# kinks_v41.net
KiCad netlist of a schematic drawn in EAGLE
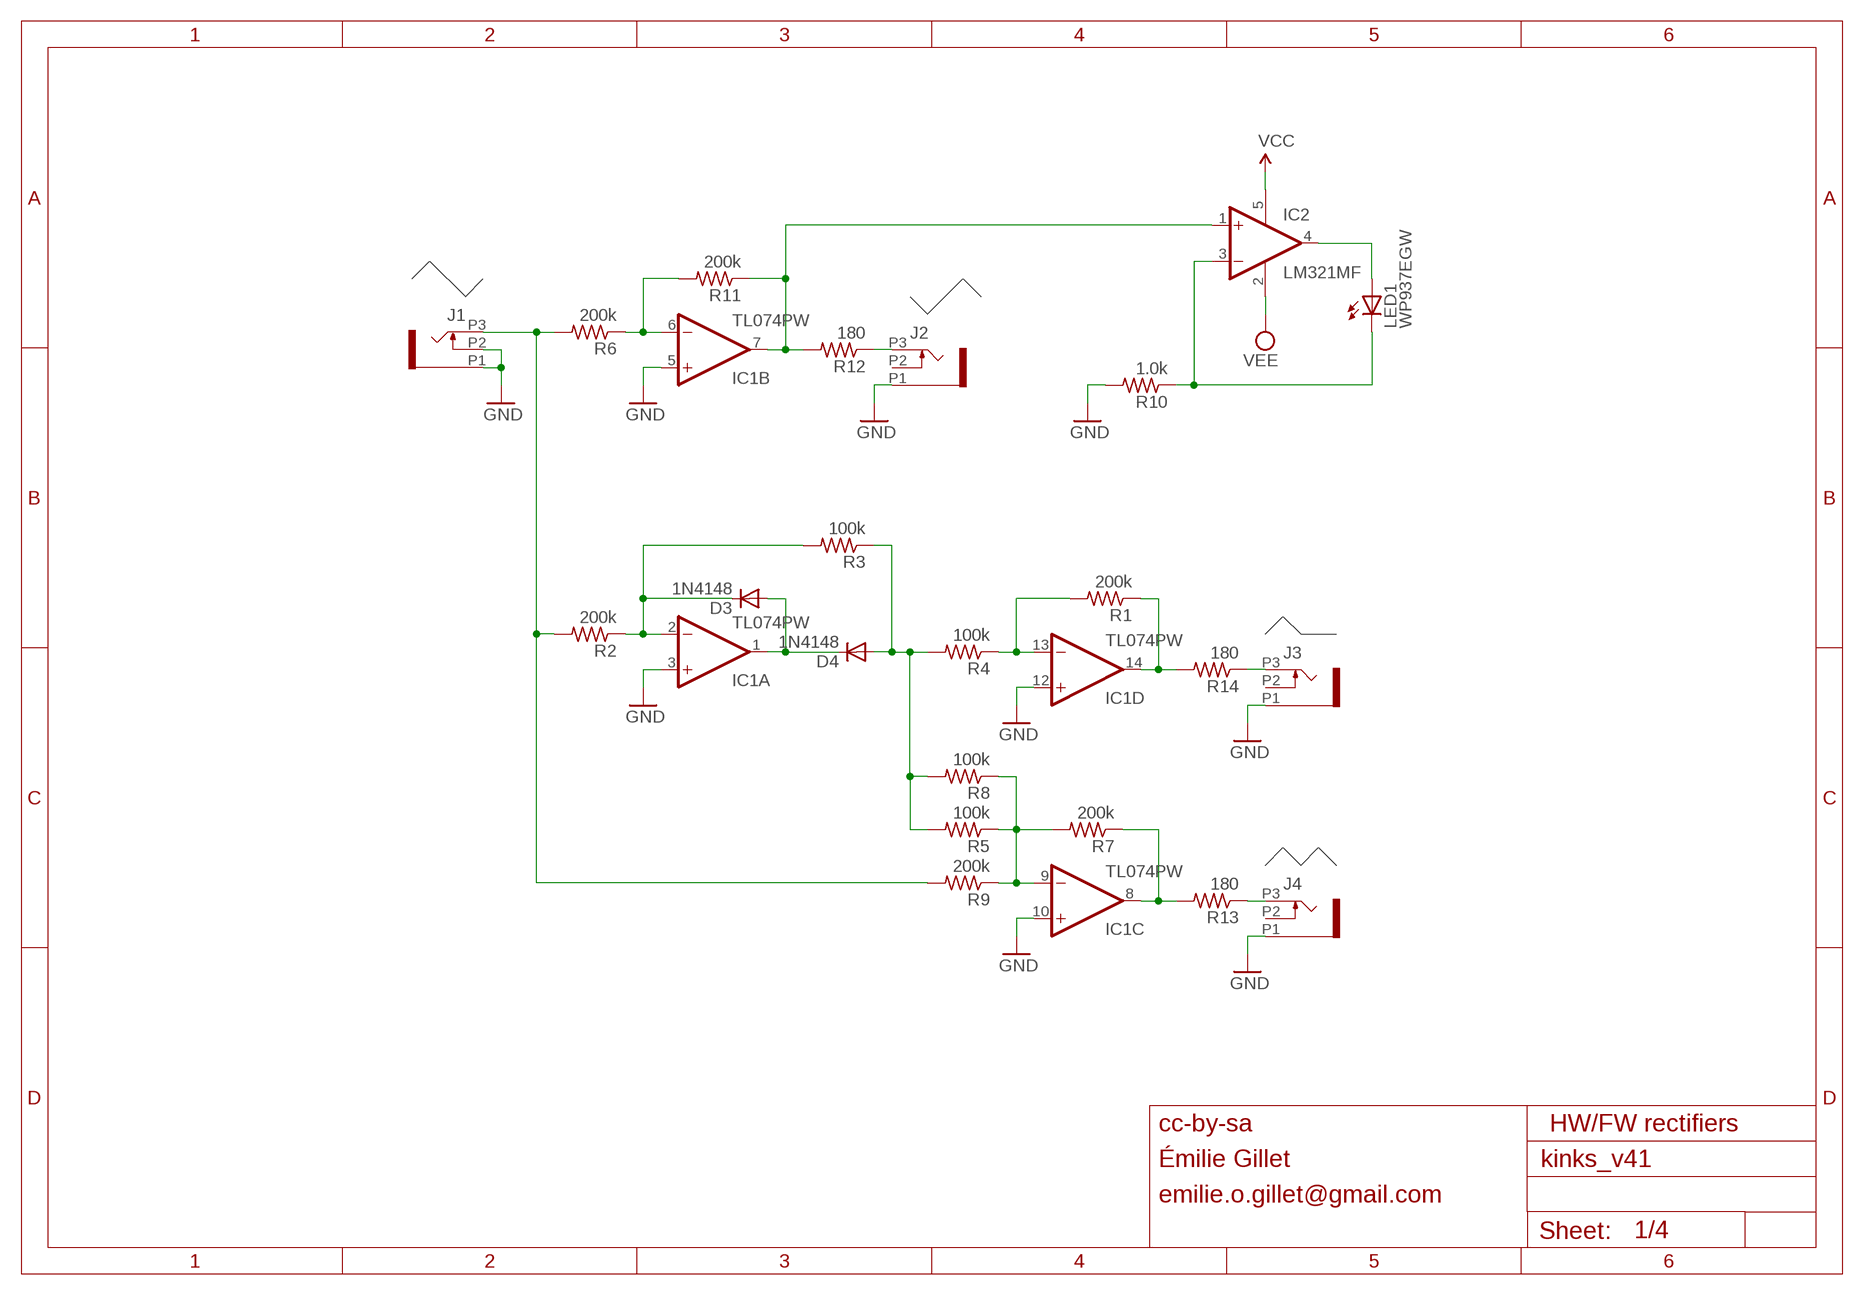
[diagram p0: schematic, sheet 1]
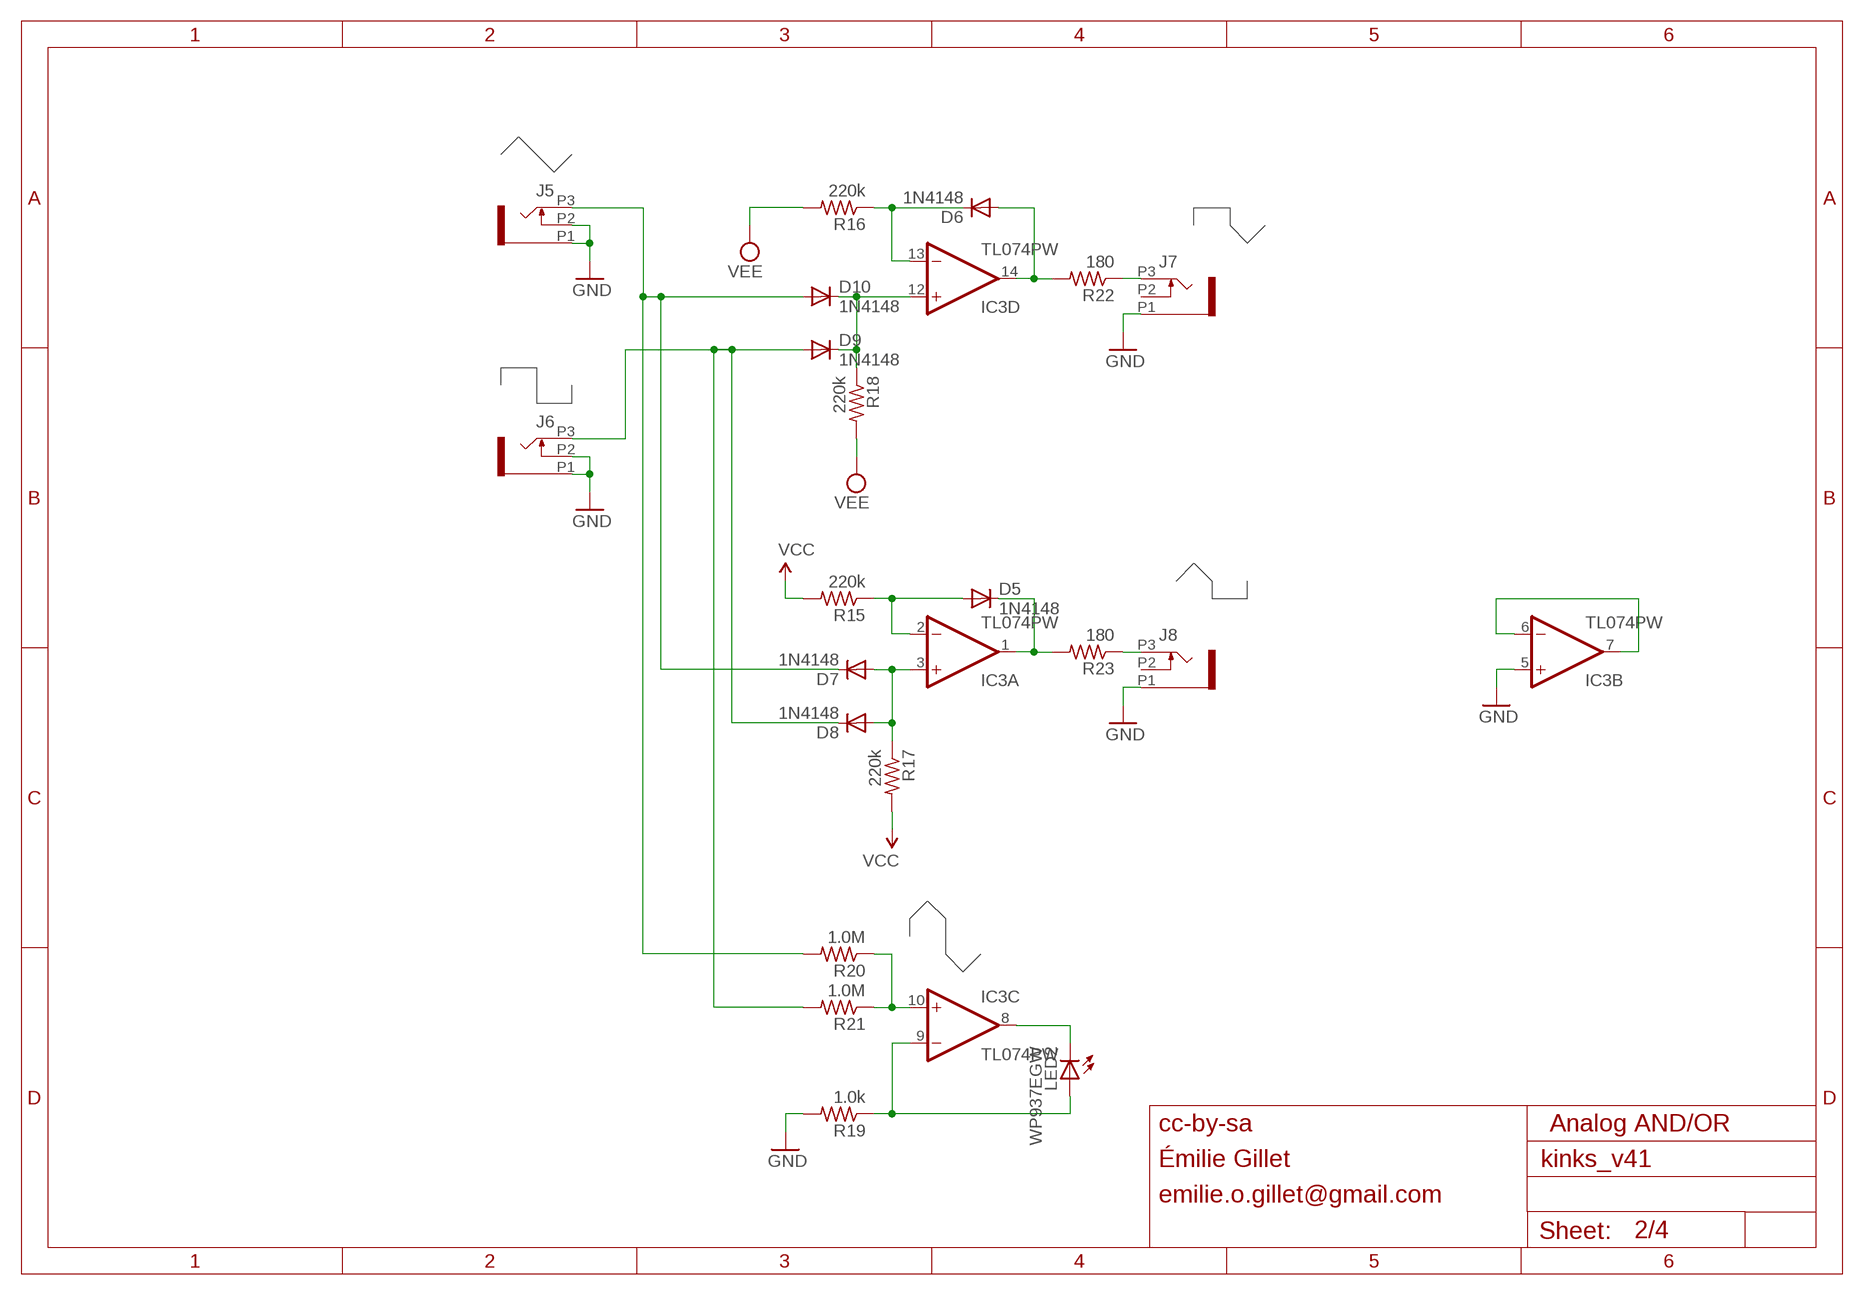
[diagram p1: schematic, sheet 2]
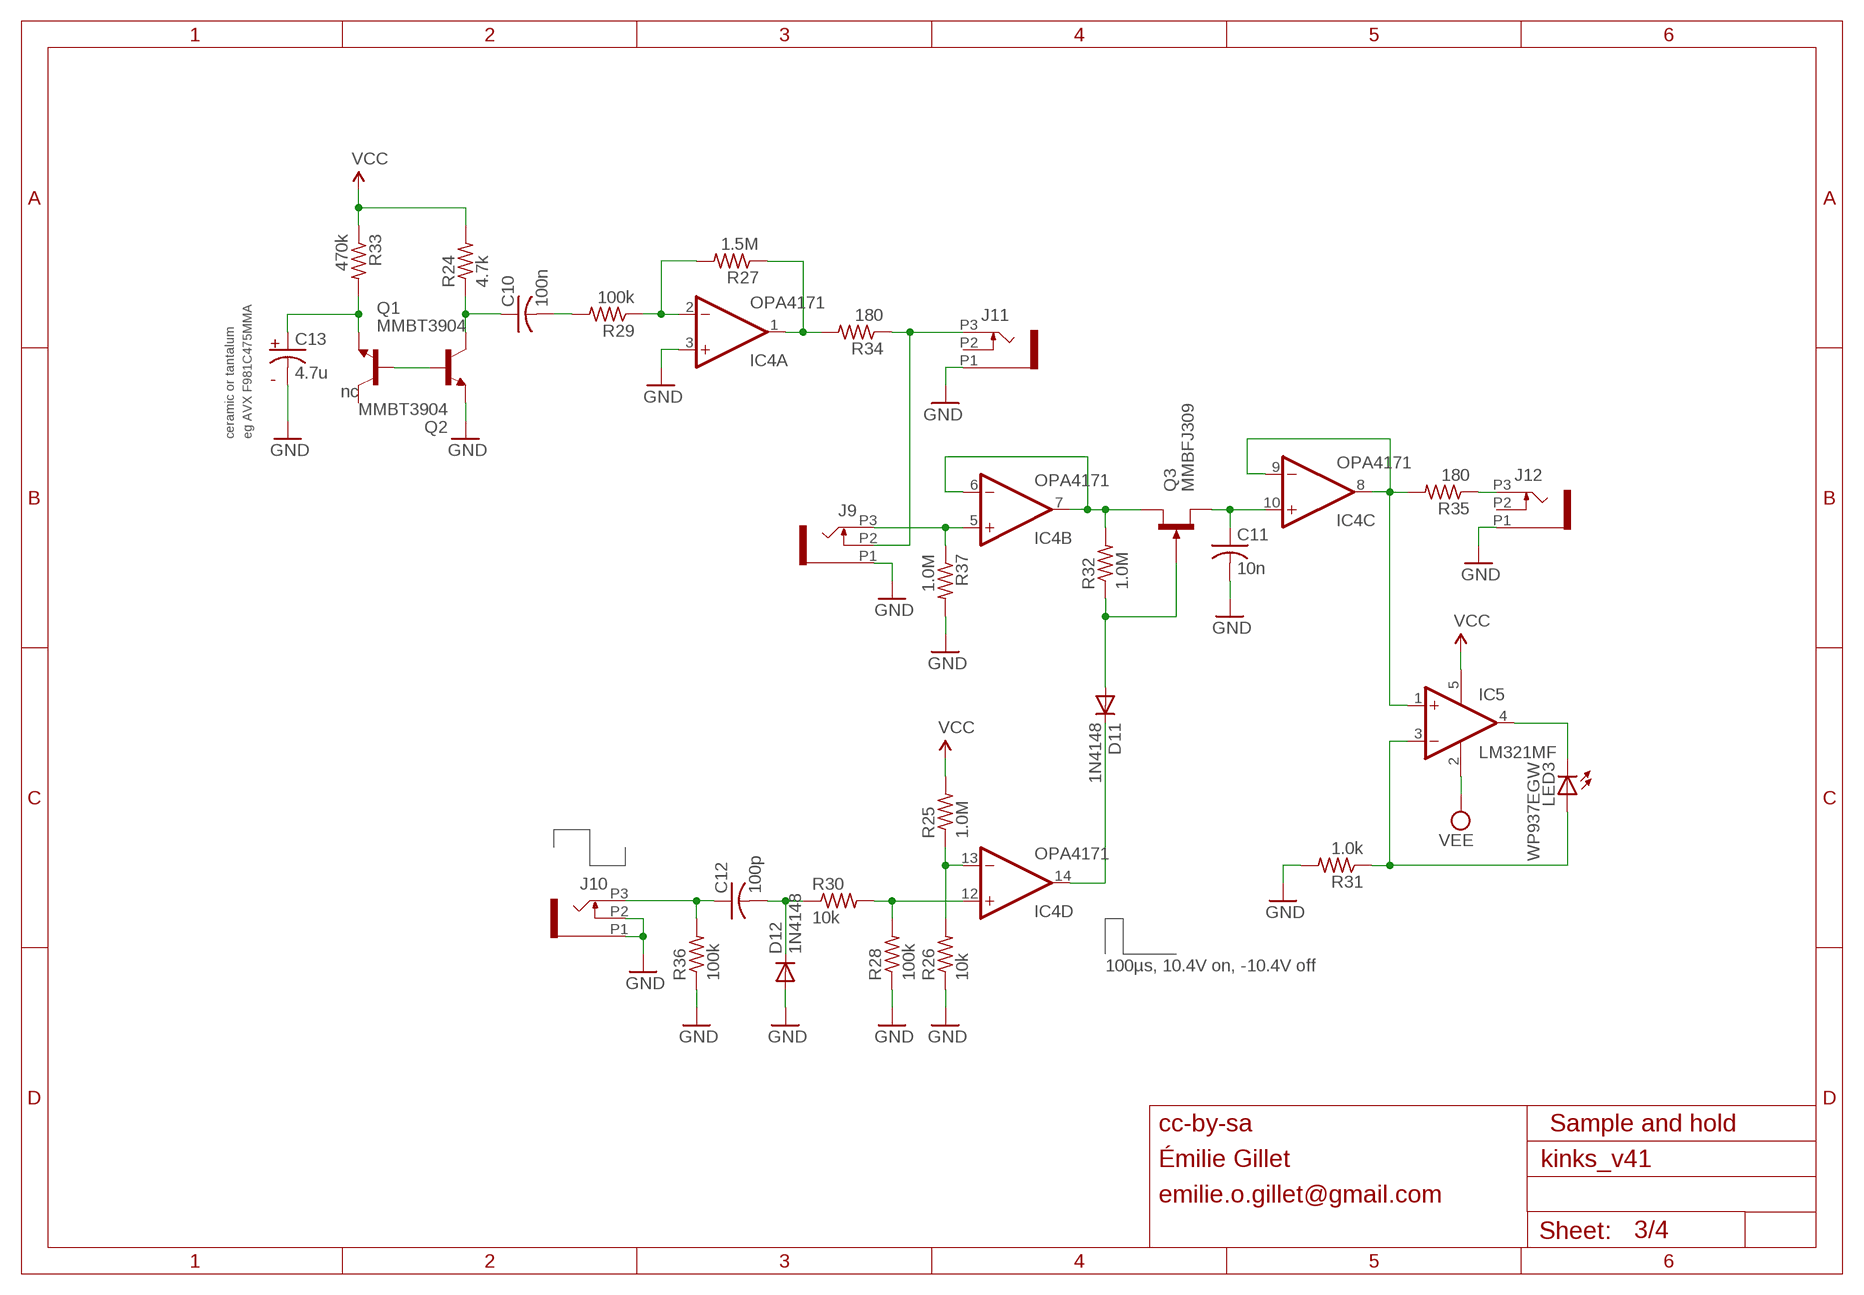
[diagram p2: schematic, sheet 3]
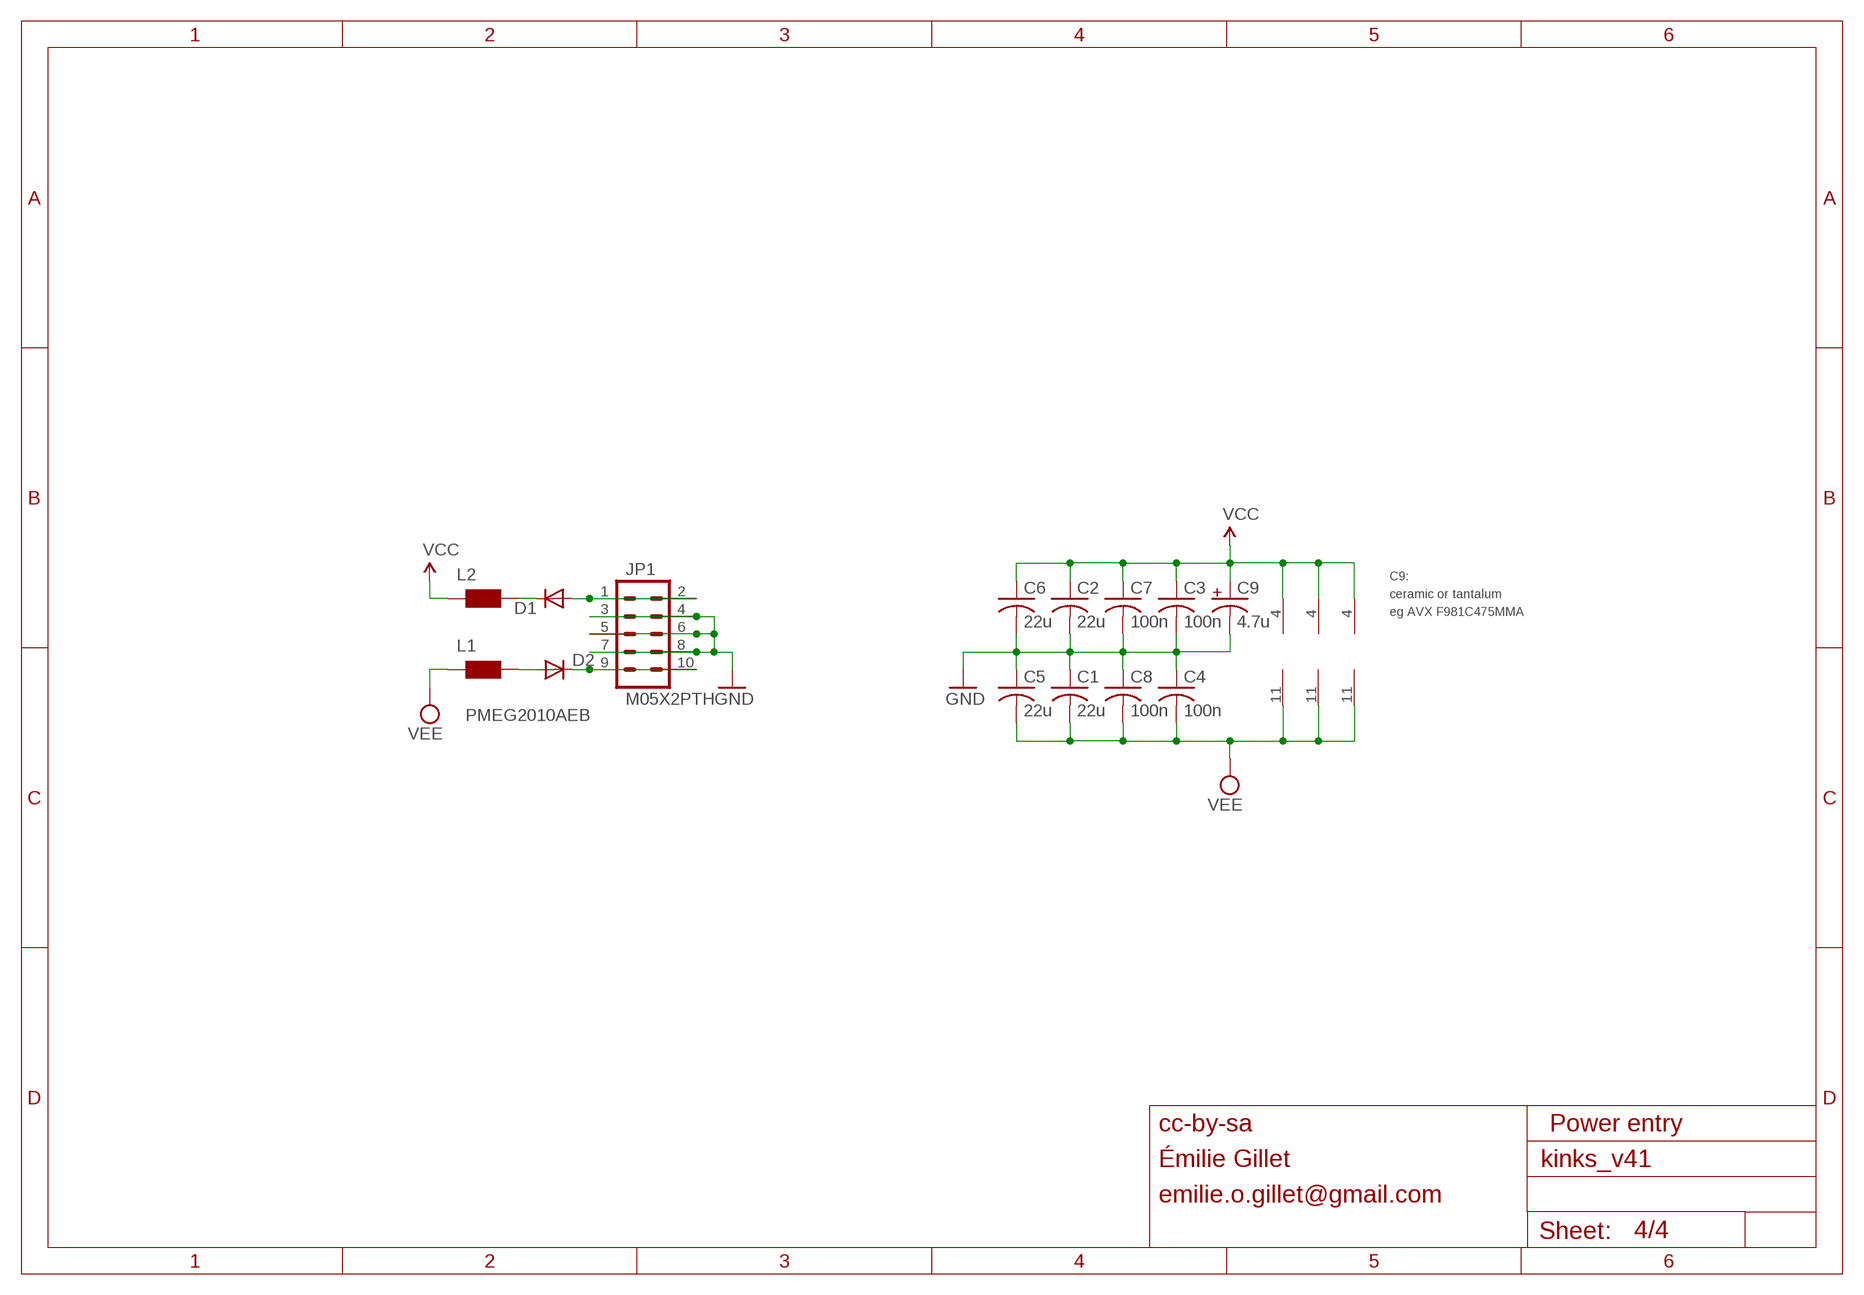
[diagram p3: schematic, sheet 4]

(export (version "E")
  (design (tool "Eeschema 10.0.6"))
  (components
    (comp (ref "C1")
      (value "22u")
      (footprint "eagle-import:C0805")
      (libsource (lib "eagle-import") (part "C-USC0805"))
    )
    (comp (ref "C2")
      (value "22u")
      (footprint "eagle-import:C0805")
      (libsource (lib "eagle-import") (part "C-USC0805"))
    )
    (comp (ref "C3")
      (value "100n")
      (footprint "eagle-import:C0402")
      (libsource (lib "eagle-import") (part "C-USC0402"))
    )
    (comp (ref "C4")
      (value "100n")
      (footprint "eagle-import:C0402")
      (libsource (lib "eagle-import") (part "C-USC0402"))
    )
    (comp (ref "C5")
      (value "22u")
      (footprint "eagle-import:C0805")
      (libsource (lib "eagle-import") (part "C-USC0805"))
    )
    (comp (ref "C6")
      (value "22u")
      (footprint "eagle-import:C0805")
      (libsource (lib "eagle-import") (part "C-USC0805"))
    )
    (comp (ref "C7")
      (value "100n")
      (footprint "eagle-import:C0402")
      (libsource (lib "eagle-import") (part "C-USC0402"))
    )
    (comp (ref "C8")
      (value "100n")
      (footprint "eagle-import:C0402")
      (libsource (lib "eagle-import") (part "C-USC0402"))
    )
    (comp (ref "C9")
      (value "4.7u")
      (footprint "eagle-import:C0603")
      (libsource (lib "eagle-import") (part "C-USC0603"))
    )
    (comp (ref "D1")
      (value "PMEG2010AEB")
      (footprint "eagle-import:SOD523")
      (libsource (lib "eagle-import") (part "DIODE-SOD523"))
    )
    (comp (ref "D2")
      (value "PMEG2010AEB")
      (footprint "eagle-import:SOD523")
      (libsource (lib "eagle-import") (part "DIODE-SOD523"))
    )
    (comp (ref "IC1")
      (value "TL074PW")
      (footprint "eagle-import:TSSOP14")
      (libsource (lib "eagle-import") (part "TL074PW"))
    )
    (comp (ref "IC3")
      (value "TL074PW")
      (footprint "eagle-import:TSSOP14")
      (libsource (lib "eagle-import") (part "TL074PW"))
    )
    (comp (ref "IC4")
      (value "OPA4171")
      (footprint "eagle-import:TSSOP14")
      (libsource (lib "eagle-import") (part "TL074PW"))
    )
    (comp (ref "JP1")
      (value "M05X2PTH")
      (footprint "eagle-import:AVR_ICSP")
      (libsource (lib "eagle-import") (part "M05X2PTH"))
    )
    (comp (ref "L1")
      (value "WE-CBF_0603")
      (footprint "eagle-import:0603")
      (libsource (lib "eagle-import") (part "WE-CBF_0603"))
    )
    (comp (ref "L2")
      (value "WE-CBF_0603")
      (footprint "eagle-import:0603")
      (libsource (lib "eagle-import") (part "WE-CBF_0603"))
    )
    (comp (ref "C10")
      (value "100n")
      (footprint "eagle-import:C0402")
      (libsource (lib "eagle-import") (part "C-USC0402"))
    )
    (comp (ref "C11")
      (value "10n")
      (footprint "eagle-import:C0603")
      (libsource (lib "eagle-import") (part "C-USC0603"))
    )
    (comp (ref "C12")
      (value "100p")
      (footprint "eagle-import:C0402")
      (libsource (lib "eagle-import") (part "C-USC0402"))
    )
    (comp (ref "C13")
      (value "4.7u")
      (footprint "eagle-import:C0603")
      (libsource (lib "eagle-import") (part "C-USC0603"))
    )
    (comp (ref "D11")
      (value "1N4148")
      (footprint "eagle-import:SOD523")
      (libsource (lib "eagle-import") (part "DIODE-SOD523"))
    )
    (comp (ref "D12")
      (value "1N4148")
      (footprint "eagle-import:SOD523")
      (libsource (lib "eagle-import") (part "DIODE-SOD523"))
    )
    (comp (ref "IC5")
      (value "LM321MF")
      (footprint "eagle-import:SOT23-5")
      (libsource (lib "eagle-import") (part "LM321?MF"))
    )
    (comp (ref "J9")
      (value "PJ301_THONKICONN6")
      (footprint "eagle-import:WQP_PJ_301M6")
      (libsource (lib "eagle-import") (part "PJ301_THONKICONN6"))
    )
    (comp (ref "J10")
      (value "PJ301_THONKICONN6")
      (footprint "eagle-import:WQP_PJ_301M6")
      (libsource (lib "eagle-import") (part "PJ301_THONKICONN6"))
    )
    (comp (ref "J11")
      (value "PJ301_THONKICONN6")
      (footprint "eagle-import:WQP_PJ_301M6")
      (libsource (lib "eagle-import") (part "PJ301_THONKICONN6"))
    )
    (comp (ref "J12")
      (value "PJ301_THONKICONN6")
      (footprint "eagle-import:WQP_PJ_301M6")
      (libsource (lib "eagle-import") (part "PJ301_THONKICONN6"))
    )
    (comp (ref "LED3")
      (value "WP937EGW")
      (footprint "eagle-import:LED3MM")
      (libsource (lib "eagle-import") (part "LED3MM"))
    )
    (comp (ref "Q1")
      (value "MMBT3904")
      (footprint "eagle-import:SOT23-BEC")
      (libsource (lib "eagle-import") (part "-NPN-SOT23-BECMMBT3904LT1"))
    )
    (comp (ref "Q2")
      (value "MMBT3904")
      (footprint "eagle-import:SOT23-BEC")
      (libsource (lib "eagle-import") (part "-NPN-SOT23-BECMMBT3904LT1"))
    )
    (comp (ref "Q3")
      (value "MMBFJ309")
      (footprint "eagle-import:SOT23")
      (libsource (lib "eagle-import") (part "MMBFJ3"))
    )
    (comp (ref "R24")
      (value "4.7k")
      (footprint "eagle-import:R0402")
      (libsource (lib "eagle-import") (part "R-US_R0402"))
    )
    (comp (ref "R25")
      (value "1.0M")
      (footprint "eagle-import:R0402")
      (libsource (lib "eagle-import") (part "R-US_R0402"))
    )
    (comp (ref "R26")
      (value "10k")
      (footprint "eagle-import:R0402")
      (libsource (lib "eagle-import") (part "R-US_R0402"))
    )
    (comp (ref "R27")
      (value "1.5M")
      (footprint "eagle-import:R0402")
      (libsource (lib "eagle-import") (part "R-US_R0402"))
    )
    (comp (ref "R28")
      (value "100k")
      (footprint "eagle-import:R0402")
      (libsource (lib "eagle-import") (part "R-US_R0402"))
    )
    (comp (ref "R29")
      (value "100k")
      (footprint "eagle-import:R0402")
      (libsource (lib "eagle-import") (part "R-US_R0402"))
    )
    (comp (ref "R30")
      (value "10k")
      (footprint "eagle-import:R0402")
      (libsource (lib "eagle-import") (part "R-US_R0402"))
    )
    (comp (ref "R31")
      (value "1.0k")
      (footprint "eagle-import:R0402")
      (libsource (lib "eagle-import") (part "R-US_R0402"))
    )
    (comp (ref "R32")
      (value "1.0M")
      (footprint "eagle-import:R0402")
      (libsource (lib "eagle-import") (part "R-US_R0402"))
    )
    (comp (ref "R33")
      (value "470k")
      (footprint "eagle-import:R0402")
      (libsource (lib "eagle-import") (part "R-US_R0402"))
    )
    (comp (ref "R34")
      (value "180")
      (footprint "eagle-import:R0402")
      (libsource (lib "eagle-import") (part "R-US_R0402"))
    )
    (comp (ref "R35")
      (value "180")
      (footprint "eagle-import:R0402")
      (libsource (lib "eagle-import") (part "R-US_R0402"))
    )
    (comp (ref "R36")
      (value "100k")
      (footprint "eagle-import:R0402")
      (libsource (lib "eagle-import") (part "R-US_R0402"))
    )
    (comp (ref "R37")
      (value "1.0M")
      (footprint "eagle-import:R0402")
      (libsource (lib "eagle-import") (part "R-US_R0402"))
    )
    (comp (ref "D5")
      (value "1N4148")
      (footprint "eagle-import:SOD523")
      (libsource (lib "eagle-import") (part "DIODE-SOD523"))
    )
    (comp (ref "D6")
      (value "1N4148")
      (footprint "eagle-import:SOD523")
      (libsource (lib "eagle-import") (part "DIODE-SOD523"))
    )
    (comp (ref "D7")
      (value "1N4148")
      (footprint "eagle-import:SOD523")
      (libsource (lib "eagle-import") (part "DIODE-SOD523"))
    )
    (comp (ref "D8")
      (value "1N4148")
      (footprint "eagle-import:SOD523")
      (libsource (lib "eagle-import") (part "DIODE-SOD523"))
    )
    (comp (ref "D9")
      (value "1N4148")
      (footprint "eagle-import:SOD523")
      (libsource (lib "eagle-import") (part "DIODE-SOD523"))
    )
    (comp (ref "D10")
      (value "1N4148")
      (footprint "eagle-import:SOD523")
      (libsource (lib "eagle-import") (part "DIODE-SOD523"))
    )
    (comp (ref "J5")
      (value "PJ301_THONKICONN6")
      (footprint "eagle-import:WQP_PJ_301M6")
      (libsource (lib "eagle-import") (part "PJ301_THONKICONN6"))
    )
    (comp (ref "J6")
      (value "PJ301_THONKICONN6")
      (footprint "eagle-import:WQP_PJ_301M6")
      (libsource (lib "eagle-import") (part "PJ301_THONKICONN6"))
    )
    (comp (ref "J7")
      (value "PJ301_THONKICONN6")
      (footprint "eagle-import:WQP_PJ_301M6")
      (libsource (lib "eagle-import") (part "PJ301_THONKICONN6"))
    )
    (comp (ref "J8")
      (value "PJ301_THONKICONN6")
      (footprint "eagle-import:WQP_PJ_301M6")
      (libsource (lib "eagle-import") (part "PJ301_THONKICONN6"))
    )
    (comp (ref "LED2")
      (value "WP937EGW")
      (footprint "eagle-import:LED3MM")
      (libsource (lib "eagle-import") (part "LED3MM"))
    )
    (comp (ref "R15")
      (value "220k")
      (footprint "eagle-import:R0402")
      (libsource (lib "eagle-import") (part "R-US_R0402"))
    )
    (comp (ref "R16")
      (value "220k")
      (footprint "eagle-import:R0402")
      (libsource (lib "eagle-import") (part "R-US_R0402"))
    )
    (comp (ref "R17")
      (value "220k")
      (footprint "eagle-import:R0402")
      (libsource (lib "eagle-import") (part "R-US_R0402"))
    )
    (comp (ref "R18")
      (value "220k")
      (footprint "eagle-import:R0402")
      (libsource (lib "eagle-import") (part "R-US_R0402"))
    )
    (comp (ref "R19")
      (value "1.0k")
      (footprint "eagle-import:R0402")
      (libsource (lib "eagle-import") (part "R-US_R0402"))
    )
    (comp (ref "R20")
      (value "1.0M")
      (footprint "eagle-import:R0402")
      (libsource (lib "eagle-import") (part "R-US_R0402"))
    )
    (comp (ref "R21")
      (value "1.0M")
      (footprint "eagle-import:R0402")
      (libsource (lib "eagle-import") (part "R-US_R0402"))
    )
    (comp (ref "R22")
      (value "180")
      (footprint "eagle-import:R0402")
      (libsource (lib "eagle-import") (part "R-US_R0402"))
    )
    (comp (ref "R23")
      (value "180")
      (footprint "eagle-import:R0402")
      (libsource (lib "eagle-import") (part "R-US_R0402"))
    )
    (comp (ref "D3")
      (value "1N4148")
      (footprint "eagle-import:SOD523")
      (libsource (lib "eagle-import") (part "DIODE-SOD523"))
    )
    (comp (ref "D4")
      (value "1N4148")
      (footprint "eagle-import:SOD523")
      (libsource (lib "eagle-import") (part "DIODE-SOD523"))
    )
    (comp (ref "IC2")
      (value "LM321MF")
      (footprint "eagle-import:SOT23-5")
      (libsource (lib "eagle-import") (part "LM321?MF"))
    )
    (comp (ref "J1")
      (value "PJ301_THONKICONN6")
      (footprint "eagle-import:WQP_PJ_301M6")
      (libsource (lib "eagle-import") (part "PJ301_THONKICONN6"))
    )
    (comp (ref "J2")
      (value "PJ301_THONKICONN6")
      (footprint "eagle-import:WQP_PJ_301M6")
      (libsource (lib "eagle-import") (part "PJ301_THONKICONN6"))
    )
    (comp (ref "J3")
      (value "PJ301_THONKICONN6")
      (footprint "eagle-import:WQP_PJ_301M6")
      (libsource (lib "eagle-import") (part "PJ301_THONKICONN6"))
    )
    (comp (ref "J4")
      (value "PJ301_THONKICONN6")
      (footprint "eagle-import:WQP_PJ_301M6")
      (libsource (lib "eagle-import") (part "PJ301_THONKICONN6"))
    )
    (comp (ref "LED1")
      (value "WP937EGW")
      (footprint "eagle-import:LED3MM")
      (libsource (lib "eagle-import") (part "LED3MM"))
    )
    (comp (ref "R1")
      (value "200k")
      (footprint "eagle-import:R0402")
      (libsource (lib "eagle-import") (part "R-US_R0402"))
    )
    (comp (ref "R2")
      (value "200k")
      (footprint "eagle-import:R0402")
      (libsource (lib "eagle-import") (part "R-US_R0402"))
    )
    (comp (ref "R3")
      (value "100k")
      (footprint "eagle-import:R0402")
      (libsource (lib "eagle-import") (part "R-US_R0402"))
    )
    (comp (ref "R4")
      (value "100k")
      (footprint "eagle-import:R0402")
      (libsource (lib "eagle-import") (part "R-US_R0402"))
    )
    (comp (ref "R5")
      (value "100k")
      (footprint "eagle-import:R0402")
      (libsource (lib "eagle-import") (part "R-US_R0402"))
    )
    (comp (ref "R6")
      (value "200k")
      (footprint "eagle-import:R0402")
      (libsource (lib "eagle-import") (part "R-US_R0402"))
    )
    (comp (ref "R7")
      (value "200k")
      (footprint "eagle-import:R0402")
      (libsource (lib "eagle-import") (part "R-US_R0402"))
    )
    (comp (ref "R8")
      (value "100k")
      (footprint "eagle-import:R0402")
      (libsource (lib "eagle-import") (part "R-US_R0402"))
    )
    (comp (ref "R9")
      (value "200k")
      (footprint "eagle-import:R0402")
      (libsource (lib "eagle-import") (part "R-US_R0402"))
    )
    (comp (ref "R10")
      (value "1.0k")
      (footprint "eagle-import:R0402")
      (libsource (lib "eagle-import") (part "R-US_R0402"))
    )
    (comp (ref "R11")
      (value "200k")
      (footprint "eagle-import:R0402")
      (libsource (lib "eagle-import") (part "R-US_R0402"))
    )
    (comp (ref "R12")
      (value "180")
      (footprint "eagle-import:R0402")
      (libsource (lib "eagle-import") (part "R-US_R0402"))
    )
    (comp (ref "R13")
      (value "180")
      (footprint "eagle-import:R0402")
      (libsource (lib "eagle-import") (part "R-US_R0402"))
    )
    (comp (ref "R14")
      (value "180")
      (footprint "eagle-import:R0402")
      (libsource (lib "eagle-import") (part "R-US_R0402"))
    )
  )
  (nets
    (net (code "1") (name "GND") (class "Default")
      (node (ref "C1") (pin "1") (pinfunction "1_1") (pintype "passive"))
      (node (ref "C11") (pin "2") (pinfunction "2_2") (pintype "passive"))
      (node (ref "C13") (pin "2") (pinfunction "2_2") (pintype "passive"))
      (node (ref "C2") (pin "2") (pinfunction "2_2") (pintype "passive"))
      (node (ref "C3") (pin "2") (pinfunction "2_2") (pintype "passive"))
      (node (ref "C4") (pin "1") (pinfunction "1_1") (pintype "passive"))
      (node (ref "C5") (pin "1") (pinfunction "1_1") (pintype "passive"))
      (node (ref "C6") (pin "2") (pinfunction "2_2") (pintype "passive"))
      (node (ref "C7") (pin "2") (pinfunction "2_2") (pintype "passive"))
      (node (ref "C8") (pin "1") (pinfunction "1_1") (pintype "passive"))
      (node (ref "C9") (pin "2") (pinfunction "2_2") (pintype "passive"))
      (node (ref "D12") (pin "A") (pinfunction "A_A") (pintype "passive"))
      (node (ref "IC1") (pin "10") (pinfunction "+IN_10") (pintype "input"))
      (node (ref "IC1") (pin "12") (pinfunction "+IN_12") (pintype "input"))
      (node (ref "IC1") (pin "3") (pinfunction "+IN_3") (pintype "input"))
      (node (ref "IC1") (pin "5") (pinfunction "+IN_5") (pintype "input"))
      (node (ref "IC3") (pin "5") (pinfunction "+IN_5") (pintype "input"))
      (node (ref "IC4") (pin "3") (pinfunction "+IN_3") (pintype "input"))
      (node (ref "J1") (pin "P1") (pinfunction "1_P1") (pintype "passive"))
      (node (ref "J1") (pin "P2") (pinfunction "2_P2") (pintype "passive"))
      (node (ref "J10") (pin "P1") (pinfunction "1_P1") (pintype "passive"))
      (node (ref "J10") (pin "P2") (pinfunction "2_P2") (pintype "passive"))
      (node (ref "J11") (pin "P1") (pinfunction "1_P1") (pintype "passive"))
      (node (ref "J12") (pin "P1") (pinfunction "1_P1") (pintype "passive"))
      (node (ref "J2") (pin "P1") (pinfunction "1_P1") (pintype "passive"))
      (node (ref "J3") (pin "P1") (pinfunction "1_P1") (pintype "passive"))
      (node (ref "J4") (pin "P1") (pinfunction "1_P1") (pintype "passive"))
      (node (ref "J5") (pin "P1") (pinfunction "1_P1") (pintype "passive"))
      (node (ref "J5") (pin "P2") (pinfunction "2_P2") (pintype "passive"))
      (node (ref "J6") (pin "P1") (pinfunction "1_P1") (pintype "passive"))
      (node (ref "J6") (pin "P2") (pinfunction "2_P2") (pintype "passive"))
      (node (ref "J7") (pin "P1") (pinfunction "1_P1") (pintype "passive"))
      (node (ref "J8") (pin "P1") (pinfunction "1_P1") (pintype "passive"))
      (node (ref "J9") (pin "P1") (pinfunction "1_P1") (pintype "passive"))
      (node (ref "JP1") (pin "3") (pinfunction "3_3") (pintype "passive"))
      (node (ref "JP1") (pin "4") (pinfunction "4_4") (pintype "passive"))
      (node (ref "JP1") (pin "5") (pinfunction "5_5") (pintype "passive"))
      (node (ref "JP1") (pin "6") (pinfunction "6_6") (pintype "passive"))
      (node (ref "JP1") (pin "7") (pinfunction "7_7") (pintype "passive"))
      (node (ref "JP1") (pin "8") (pinfunction "8_8") (pintype "passive"))
      (node (ref "Q1") (pin "E") (pinfunction "E_E") (pintype "passive"))
      (node (ref "R10") (pin "2") (pinfunction "2_2") (pintype "passive"))
      (node (ref "R19") (pin "2") (pinfunction "2_2") (pintype "passive"))
      (node (ref "R26") (pin "1") (pinfunction "1_1") (pintype "passive"))
      (node (ref "R28") (pin "1") (pinfunction "1_1") (pintype "passive"))
      (node (ref "R31") (pin "2") (pinfunction "2_2") (pintype "passive"))
      (node (ref "R36") (pin "1") (pinfunction "1_1") (pintype "passive"))
      (node (ref "R37") (pin "2") (pinfunction "2_2") (pintype "passive"))
    )
    (net (code "2") (name "Net-(C10-Pad1)") (class "Default")
      (node (ref "C10") (pin "1") (pinfunction "1_1") (pintype "passive"))
      (node (ref "Q1") (pin "C") (pinfunction "C_C") (pintype "passive"))
      (node (ref "R24") (pin "1") (pinfunction "1_1") (pintype "passive"))
    )
    (net (code "3") (name "Net-(C10-Pad2)") (class "Default")
      (node (ref "C10") (pin "2") (pinfunction "2_2") (pintype "passive"))
      (node (ref "R29") (pin "2") (pinfunction "2_2") (pintype "passive"))
    )
    (net (code "4") (name "Net-(C12-Pad2)") (class "Default")
      (node (ref "C12") (pin "2") (pinfunction "2_2") (pintype "passive"))
      (node (ref "D12") (pin "C") (pinfunction "C_C") (pintype "passive"))
      (node (ref "R30") (pin "1") (pinfunction "1_1") (pintype "passive"))
    )
    (net (code "5") (name "Net-(C13-Pad1)") (class "Default")
      (node (ref "C13") (pin "1") (pinfunction "1_1") (pintype "passive"))
      (node (ref "Q2") (pin "E") (pinfunction "E_E") (pintype "passive"))
      (node (ref "R33") (pin "2") (pinfunction "2_2") (pintype "passive"))
    )
    (net (code "6") (name "Net-(D1-PadA)") (class "Default")
      (node (ref "D1") (pin "A") (pinfunction "A_A") (pintype "passive"))
      (node (ref "JP1") (pin "1") (pinfunction "1_1") (pintype "passive"))
      (node (ref "JP1") (pin "2") (pinfunction "2_2") (pintype "passive"))
    )
    (net (code "7") (name "Net-(D1-PadC)") (class "Default")
      (node (ref "D1") (pin "C") (pinfunction "C_C") (pintype "passive"))
      (node (ref "L2") (pin "2") (pinfunction "2_2") (pintype "passive"))
    )
    (net (code "8") (name "Net-(D2-PadA)") (class "Default")
      (node (ref "D2") (pin "A") (pinfunction "A_A") (pintype "passive"))
      (node (ref "L1") (pin "2") (pinfunction "2_2") (pintype "passive"))
    )
    (net (code "9") (name "Net-(D2-PadC)") (class "Default")
      (node (ref "D2") (pin "C") (pinfunction "C_C") (pintype "passive"))
      (node (ref "JP1") (pin "10") (pinfunction "10_10") (pintype "passive"))
      (node (ref "JP1") (pin "9") (pinfunction "9_9") (pintype "passive"))
    )
    (net (code "10") (name "Net-(D4-PadA)") (class "Default")
      (node (ref "D4") (pin "A") (pinfunction "A_A") (pintype "passive"))
      (node (ref "R3") (pin "1") (pinfunction "1_1") (pintype "passive"))
      (node (ref "R4") (pin "2") (pinfunction "2_2") (pintype "passive"))
      (node (ref "R5") (pin "2") (pinfunction "2_2") (pintype "passive"))
      (node (ref "R8") (pin "2") (pinfunction "2_2") (pintype "passive"))
    )
    (net (code "11") (name "Net-(IC1A--IN)") (class "Default")
      (node (ref "D3") (pin "C") (pinfunction "C_C") (pintype "passive"))
      (node (ref "IC1") (pin "2") (pinfunction "-IN_2") (pintype "input"))
      (node (ref "R2") (pin "1") (pinfunction "1_1") (pintype "passive"))
      (node (ref "R3") (pin "2") (pinfunction "2_2") (pintype "passive"))
    )
    (net (code "12") (name "Net-(IC1A-OUT)") (class "Default")
      (node (ref "D3") (pin "A") (pinfunction "A_A") (pintype "passive"))
      (node (ref "D4") (pin "C") (pinfunction "C_C") (pintype "passive"))
      (node (ref "IC1") (pin "1") (pinfunction "OUT_1") (pintype "output"))
    )
    (net (code "13") (name "Net-(IC1B--IN)") (class "Default")
      (node (ref "IC1") (pin "6") (pinfunction "-IN_6") (pintype "input"))
      (node (ref "R11") (pin "2") (pinfunction "2_2") (pintype "passive"))
      (node (ref "R6") (pin "1") (pinfunction "1_1") (pintype "passive"))
    )
    (net (code "14") (name "Net-(IC1B-OUT)") (class "Default")
      (node (ref "IC1") (pin "7") (pinfunction "OUT_7") (pintype "output"))
      (node (ref "IC2") (pin "1") (pinfunction "+IN_1") (pintype "input"))
      (node (ref "R11") (pin "1") (pinfunction "1_1") (pintype "passive"))
      (node (ref "R12") (pin "2") (pinfunction "2_2") (pintype "passive"))
    )
    (net (code "15") (name "Net-(IC1C--IN)") (class "Default")
      (node (ref "IC1") (pin "9") (pinfunction "-IN_9") (pintype "input"))
      (node (ref "R5") (pin "1") (pinfunction "1_1") (pintype "passive"))
      (node (ref "R7") (pin "2") (pinfunction "2_2") (pintype "passive"))
      (node (ref "R8") (pin "1") (pinfunction "1_1") (pintype "passive"))
      (node (ref "R9") (pin "1") (pinfunction "1_1") (pintype "passive"))
    )
    (net (code "16") (name "Net-(IC1C-OUT)") (class "Default")
      (node (ref "IC1") (pin "8") (pinfunction "OUT_8") (pintype "output"))
      (node (ref "R13") (pin "2") (pinfunction "2_2") (pintype "passive"))
      (node (ref "R7") (pin "1") (pinfunction "1_1") (pintype "passive"))
    )
    (net (code "17") (name "Net-(IC1D--IN)") (class "Default")
      (node (ref "IC1") (pin "13") (pinfunction "-IN_13") (pintype "input"))
      (node (ref "R1") (pin "2") (pinfunction "2_2") (pintype "passive"))
      (node (ref "R4") (pin "1") (pinfunction "1_1") (pintype "passive"))
    )
    (net (code "18") (name "Net-(IC1D-OUT)") (class "Default")
      (node (ref "IC1") (pin "14") (pinfunction "OUT_14") (pintype "output"))
      (node (ref "R1") (pin "1") (pinfunction "1_1") (pintype "passive"))
      (node (ref "R14") (pin "2") (pinfunction "2_2") (pintype "passive"))
    )
    (net (code "19") (name "Net-(IC2--IN)") (class "Default")
      (node (ref "IC2") (pin "3") (pinfunction "-IN_3") (pintype "input"))
      (node (ref "LED1") (pin "K") (pinfunction "C_K") (pintype "passive"))
      (node (ref "R10") (pin "1") (pinfunction "1_1") (pintype "passive"))
    )
    (net (code "20") (name "Net-(IC2-OUT)") (class "Default")
      (node (ref "IC2") (pin "4") (pinfunction "OUT_4") (pintype "output"))
      (node (ref "LED1") (pin "A") (pinfunction "A_A") (pintype "passive"))
    )
    (net (code "21") (name "Net-(IC3A-+IN)") (class "Default")
      (node (ref "D7") (pin "A") (pinfunction "A_A") (pintype "passive"))
      (node (ref "D8") (pin "A") (pinfunction "A_A") (pintype "passive"))
      (node (ref "IC3") (pin "3") (pinfunction "+IN_3") (pintype "input"))
      (node (ref "R17") (pin "1") (pinfunction "1_1") (pintype "passive"))
    )
    (net (code "22") (name "Net-(IC3A--IN)") (class "Default")
      (node (ref "D5") (pin "A") (pinfunction "A_A") (pintype "passive"))
      (node (ref "IC3") (pin "2") (pinfunction "-IN_2") (pintype "input"))
      (node (ref "R15") (pin "1") (pinfunction "1_1") (pintype "passive"))
    )
    (net (code "23") (name "Net-(IC3A-OUT)") (class "Default")
      (node (ref "D5") (pin "C") (pinfunction "C_C") (pintype "passive"))
      (node (ref "IC3") (pin "1") (pinfunction "OUT_1") (pintype "output"))
      (node (ref "R23") (pin "2") (pinfunction "2_2") (pintype "passive"))
    )
    (net (code "24") (name "Net-(IC3B--IN)") (class "Default")
      (node (ref "IC3") (pin "6") (pinfunction "-IN_6") (pintype "input"))
      (node (ref "IC3") (pin "7") (pinfunction "OUT_7") (pintype "output"))
    )
    (net (code "25") (name "Net-(IC3C-+IN)") (class "Default")
      (node (ref "IC3") (pin "10") (pinfunction "+IN_10") (pintype "input"))
      (node (ref "R20") (pin "1") (pinfunction "1_1") (pintype "passive"))
      (node (ref "R21") (pin "1") (pinfunction "1_1") (pintype "passive"))
    )
    (net (code "26") (name "Net-(IC3C--IN)") (class "Default")
      (node (ref "IC3") (pin "9") (pinfunction "-IN_9") (pintype "input"))
      (node (ref "LED2") (pin "A") (pinfunction "A_A") (pintype "passive"))
      (node (ref "R19") (pin "1") (pinfunction "1_1") (pintype "passive"))
    )
    (net (code "27") (name "Net-(IC3C-OUT)") (class "Default")
      (node (ref "IC3") (pin "8") (pinfunction "OUT_8") (pintype "output"))
      (node (ref "LED2") (pin "K") (pinfunction "C_K") (pintype "passive"))
    )
    (net (code "28") (name "Net-(IC3D-+IN)") (class "Default")
      (node (ref "D10") (pin "C") (pinfunction "C_C") (pintype "passive"))
      (node (ref "D9") (pin "C") (pinfunction "C_C") (pintype "passive"))
      (node (ref "IC3") (pin "12") (pinfunction "+IN_12") (pintype "input"))
      (node (ref "R18") (pin "1") (pinfunction "1_1") (pintype "passive"))
    )
    (net (code "29") (name "Net-(IC3D--IN)") (class "Default")
      (node (ref "D6") (pin "C") (pinfunction "C_C") (pintype "passive"))
      (node (ref "IC3") (pin "13") (pinfunction "-IN_13") (pintype "input"))
      (node (ref "R16") (pin "1") (pinfunction "1_1") (pintype "passive"))
    )
    (net (code "30") (name "Net-(IC3D-OUT)") (class "Default")
      (node (ref "D6") (pin "A") (pinfunction "A_A") (pintype "passive"))
      (node (ref "IC3") (pin "14") (pinfunction "OUT_14") (pintype "output"))
      (node (ref "R22") (pin "2") (pinfunction "2_2") (pintype "passive"))
    )
    (net (code "31") (name "Net-(IC4A--IN)") (class "Default")
      (node (ref "IC4") (pin "2") (pinfunction "-IN_2") (pintype "input"))
      (node (ref "R27") (pin "2") (pinfunction "2_2") (pintype "passive"))
      (node (ref "R29") (pin "1") (pinfunction "1_1") (pintype "passive"))
    )
    (net (code "32") (name "Net-(IC4A-OUT)") (class "Default")
      (node (ref "IC4") (pin "1") (pinfunction "OUT_1") (pintype "output"))
      (node (ref "R27") (pin "1") (pinfunction "1_1") (pintype "passive"))
      (node (ref "R34") (pin "2") (pinfunction "2_2") (pintype "passive"))
    )
    (net (code "33") (name "Net-(IC4B-+IN)") (class "Default")
      (node (ref "IC4") (pin "5") (pinfunction "+IN_5") (pintype "input"))
      (node (ref "J9") (pin "P3") (pinfunction "3_P3") (pintype "passive"))
      (node (ref "R37") (pin "1") (pinfunction "1_1") (pintype "passive"))
    )
    (net (code "34") (name "Net-(IC4B--IN)") (class "Default")
      (node (ref "IC4") (pin "6") (pinfunction "-IN_6") (pintype "input"))
      (node (ref "IC4") (pin "7") (pinfunction "OUT_7") (pintype "output"))
      (node (ref "Q3") (pin "1") (pinfunction "D_1") (pintype "passive"))
      (node (ref "R32") (pin "2") (pinfunction "2_2") (pintype "passive"))
    )
    (net (code "35") (name "Net-(IC4C-+IN)") (class "Default")
      (node (ref "C11") (pin "1") (pinfunction "1_1") (pintype "passive"))
      (node (ref "IC4") (pin "10") (pinfunction "+IN_10") (pintype "input"))
      (node (ref "Q3") (pin "2") (pinfunction "S_2") (pintype "passive"))
    )
    (net (code "36") (name "Net-(IC4C--IN)") (class "Default")
      (node (ref "IC4") (pin "8") (pinfunction "OUT_8") (pintype "output"))
      (node (ref "IC4") (pin "9") (pinfunction "-IN_9") (pintype "input"))
      (node (ref "IC5") (pin "1") (pinfunction "+IN_1") (pintype "input"))
      (node (ref "R35") (pin "2") (pinfunction "2_2") (pintype "passive"))
    )
    (net (code "37") (name "Net-(IC4D-+IN)") (class "Default")
      (node (ref "IC4") (pin "12") (pinfunction "+IN_12") (pintype "input"))
      (node (ref "R28") (pin "2") (pinfunction "2_2") (pintype "passive"))
      (node (ref "R30") (pin "2") (pinfunction "2_2") (pintype "passive"))
    )
    (net (code "38") (name "Net-(IC4D--IN)") (class "Default")
      (node (ref "IC4") (pin "13") (pinfunction "-IN_13") (pintype "input"))
      (node (ref "R25") (pin "1") (pinfunction "1_1") (pintype "passive"))
      (node (ref "R26") (pin "2") (pinfunction "2_2") (pintype "passive"))
    )
    (net (code "39") (name "Net-(IC4D-OUT)") (class "Default")
      (node (ref "D11") (pin "C") (pinfunction "C_C") (pintype "passive"))
      (node (ref "IC4") (pin "14") (pinfunction "OUT_14") (pintype "output"))
    )
    (net (code "40") (name "Net-(IC5--IN)") (class "Default")
      (node (ref "IC5") (pin "3") (pinfunction "-IN_3") (pintype "input"))
      (node (ref "LED3") (pin "A") (pinfunction "A_A") (pintype "passive"))
      (node (ref "R31") (pin "1") (pinfunction "1_1") (pintype "passive"))
    )
    (net (code "41") (name "Net-(IC5-OUT)") (class "Default")
      (node (ref "IC5") (pin "4") (pinfunction "OUT_4") (pintype "output"))
      (node (ref "LED3") (pin "K") (pinfunction "C_K") (pintype "passive"))
    )
    (net (code "42") (name "Net-(J1-3)") (class "Default")
      (node (ref "J1") (pin "P3") (pinfunction "3_P3") (pintype "passive"))
      (node (ref "R2") (pin "2") (pinfunction "2_2") (pintype "passive"))
      (node (ref "R6") (pin "2") (pinfunction "2_2") (pintype "passive"))
      (node (ref "R9") (pin "2") (pinfunction "2_2") (pintype "passive"))
    )
    (net (code "43") (name "Net-(J2-3)") (class "Default")
      (node (ref "J2") (pin "P3") (pinfunction "3_P3") (pintype "passive"))
      (node (ref "R12") (pin "1") (pinfunction "1_1") (pintype "passive"))
    )
    (net (code "44") (name "Net-(J3-3)") (class "Default")
      (node (ref "J3") (pin "P3") (pinfunction "3_P3") (pintype "passive"))
      (node (ref "R14") (pin "1") (pinfunction "1_1") (pintype "passive"))
    )
    (net (code "45") (name "Net-(J4-3)") (class "Default")
      (node (ref "J4") (pin "P3") (pinfunction "3_P3") (pintype "passive"))
      (node (ref "R13") (pin "1") (pinfunction "1_1") (pintype "passive"))
    )
    (net (code "46") (name "Net-(J5-3)") (class "Default")
      (node (ref "D10") (pin "A") (pinfunction "A_A") (pintype "passive"))
      (node (ref "D7") (pin "C") (pinfunction "C_C") (pintype "passive"))
      (node (ref "J5") (pin "P3") (pinfunction "3_P3") (pintype "passive"))
      (node (ref "R20") (pin "2") (pinfunction "2_2") (pintype "passive"))
    )
    (net (code "47") (name "Net-(J6-3)") (class "Default")
      (node (ref "D8") (pin "C") (pinfunction "C_C") (pintype "passive"))
      (node (ref "D9") (pin "A") (pinfunction "A_A") (pintype "passive"))
      (node (ref "J6") (pin "P3") (pinfunction "3_P3") (pintype "passive"))
      (node (ref "R21") (pin "2") (pinfunction "2_2") (pintype "passive"))
    )
    (net (code "48") (name "Net-(J7-3)") (class "Default")
      (node (ref "J7") (pin "P3") (pinfunction "3_P3") (pintype "passive"))
      (node (ref "R22") (pin "1") (pinfunction "1_1") (pintype "passive"))
    )
    (net (code "49") (name "Net-(J8-3)") (class "Default")
      (node (ref "J8") (pin "P3") (pinfunction "3_P3") (pintype "passive"))
      (node (ref "R23") (pin "1") (pinfunction "1_1") (pintype "passive"))
    )
    (net (code "50") (name "Net-(J10-3)") (class "Default")
      (node (ref "C12") (pin "1") (pinfunction "1_1") (pintype "passive"))
      (node (ref "J10") (pin "P3") (pinfunction "3_P3") (pintype "passive"))
      (node (ref "R36") (pin "2") (pinfunction "2_2") (pintype "passive"))
    )
    (net (code "51") (name "Net-(J11-3)") (class "Default")
      (node (ref "J11") (pin "P3") (pinfunction "3_P3") (pintype "passive"))
      (node (ref "J9") (pin "P2") (pinfunction "2_P2") (pintype "passive"))
      (node (ref "R34") (pin "1") (pinfunction "1_1") (pintype "passive"))
    )
    (net (code "52") (name "Net-(J12-3)") (class "Default")
      (node (ref "J12") (pin "P3") (pinfunction "3_P3") (pintype "passive"))
      (node (ref "R35") (pin "1") (pinfunction "1_1") (pintype "passive"))
    )
    (net (code "53") (name "Net-(Q1-PadB)") (class "Default")
      (node (ref "Q1") (pin "B") (pinfunction "B_B") (pintype "passive"))
      (node (ref "Q2") (pin "B") (pinfunction "B_B") (pintype "passive"))
    )
    (net (code "54") (name "Net-(Q3-G)") (class "Default")
      (node (ref "D11") (pin "A") (pinfunction "A_A") (pintype "passive"))
      (node (ref "Q3") (pin "3") (pinfunction "G_3") (pintype "passive"))
      (node (ref "R32") (pin "1") (pinfunction "1_1") (pintype "passive"))
    )
    (net (code "55") (name "VCC") (class "Default")
      (node (ref "C2") (pin "1") (pinfunction "1_1") (pintype "passive"))
      (node (ref "C3") (pin "1") (pinfunction "1_1") (pintype "passive"))
      (node (ref "C6") (pin "1") (pinfunction "1_1") (pintype "passive"))
      (node (ref "C7") (pin "1") (pinfunction "1_1") (pintype "passive"))
      (node (ref "C9") (pin "1") (pinfunction "1_1") (pintype "passive"))
      (node (ref "IC1") (pin "4") (pinfunction "V+_4") (pintype "power_in"))
      (node (ref "IC2") (pin "5") (pinfunction "V+_5") (pintype "power_in"))
      (node (ref "IC3") (pin "4") (pinfunction "V+_4") (pintype "power_in"))
      (node (ref "IC4") (pin "4") (pinfunction "V+_4") (pintype "power_in"))
      (node (ref "IC5") (pin "5") (pinfunction "V+_5") (pintype "power_in"))
      (node (ref "L2") (pin "1") (pinfunction "1_1") (pintype "passive"))
      (node (ref "R15") (pin "2") (pinfunction "2_2") (pintype "passive"))
      (node (ref "R17") (pin "2") (pinfunction "2_2") (pintype "passive"))
      (node (ref "R24") (pin "2") (pinfunction "2_2") (pintype "passive"))
      (node (ref "R25") (pin "2") (pinfunction "2_2") (pintype "passive"))
      (node (ref "R33") (pin "1") (pinfunction "1_1") (pintype "passive"))
    )
    (net (code "56") (name "VEE") (class "Default")
      (node (ref "C1") (pin "2") (pinfunction "2_2") (pintype "passive"))
      (node (ref "C4") (pin "2") (pinfunction "2_2") (pintype "passive"))
      (node (ref "C5") (pin "2") (pinfunction "2_2") (pintype "passive"))
      (node (ref "C8") (pin "2") (pinfunction "2_2") (pintype "passive"))
      (node (ref "IC1") (pin "11") (pinfunction "V-_11") (pintype "power_in"))
      (node (ref "IC2") (pin "2") (pinfunction "V-_2") (pintype "power_in"))
      (node (ref "IC3") (pin "11") (pinfunction "V-_11") (pintype "power_in"))
      (node (ref "IC4") (pin "11") (pinfunction "V-_11") (pintype "power_in"))
      (node (ref "IC5") (pin "2") (pinfunction "V-_2") (pintype "power_in"))
      (node (ref "L1") (pin "1") (pinfunction "1_1") (pintype "passive"))
      (node (ref "R16") (pin "2") (pinfunction "2_2") (pintype "passive"))
      (node (ref "R18") (pin "2") (pinfunction "2_2") (pintype "passive"))
    )
    (net (code "57") (name "unconnected-(J2-2-PadP2)") (class "Default")
      (node (ref "J2") (pin "P2") (pinfunction "2_P2") (pintype "passive"))
    )
    (net (code "58") (name "unconnected-(J3-2-PadP2)") (class "Default")
      (node (ref "J3") (pin "P2") (pinfunction "2_P2") (pintype "passive"))
    )
    (net (code "59") (name "unconnected-(J4-2-PadP2)") (class "Default")
      (node (ref "J4") (pin "P2") (pinfunction "2_P2") (pintype "passive"))
    )
    (net (code "60") (name "unconnected-(J7-2-PadP2)") (class "Default")
      (node (ref "J7") (pin "P2") (pinfunction "2_P2") (pintype "passive"))
    )
    (net (code "61") (name "unconnected-(J8-2-PadP2)") (class "Default")
      (node (ref "J8") (pin "P2") (pinfunction "2_P2") (pintype "passive"))
    )
    (net (code "62") (name "unconnected-(J11-2-PadP2)") (class "Default")
      (node (ref "J11") (pin "P2") (pinfunction "2_P2") (pintype "passive"))
    )
    (net (code "63") (name "unconnected-(J12-2-PadP2)") (class "Default")
      (node (ref "J12") (pin "P2") (pinfunction "2_P2") (pintype "passive"))
    )
    (net (code "64") (name "unconnected-(Q2-PadC)") (class "Default")
      (node (ref "Q2") (pin "C") (pinfunction "C_C") (pintype "passive"))
    )
  )
)
